# team_flag_jig.net
KiCad netlist of a schematic drawn in EAGLE
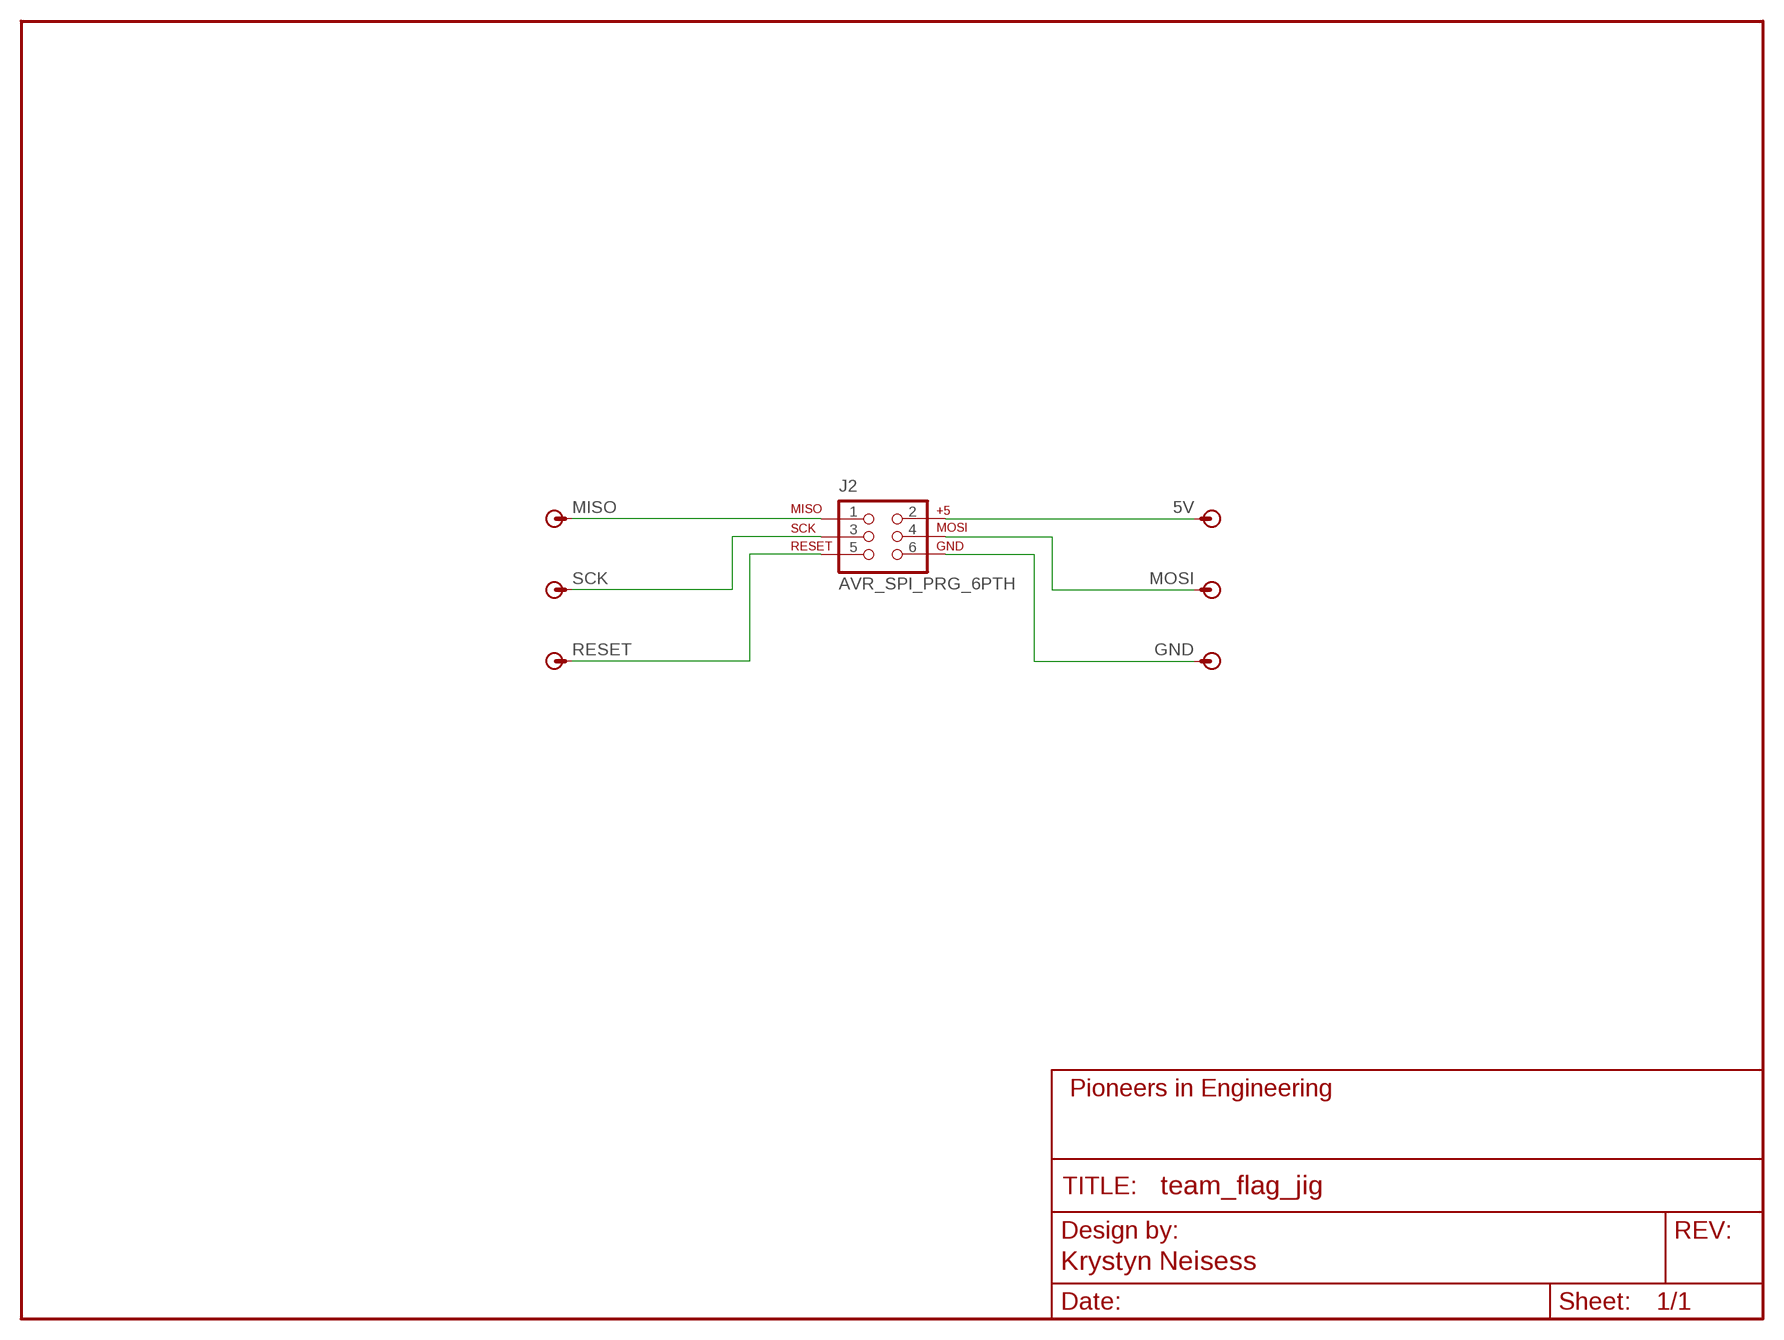
[diagram p0: schematic, sheet 1]

(export (version "E")
  (design (tool "Eeschema 10.0.6"))
  (components
    (comp (ref "5V")
      (value "POGO_PIN")
      (footprint "eagle-import:POGO_PIN_394")
      (libsource (lib "eagle-import") (part "POGO_PIN"))
    )
    (comp (ref "GND")
      (value "POGO_PIN")
      (footprint "eagle-import:POGO_PIN_394")
      (libsource (lib "eagle-import") (part "POGO_PIN"))
    )
    (comp (ref "J2")
      (value "AVR_SPI_PRG_6PTH")
      (footprint "eagle-import:2X3")
      (libsource (lib "eagle-import") (part "AVR_SPI_PRG_6PTH"))
    )
    (comp (ref "MISO")
      (value "POGO_PIN")
      (footprint "eagle-import:POGO_PIN_394")
      (libsource (lib "eagle-import") (part "POGO_PIN"))
    )
    (comp (ref "MOSI")
      (value "POGO_PIN")
      (footprint "eagle-import:POGO_PIN_394")
      (libsource (lib "eagle-import") (part "POGO_PIN"))
    )
    (comp (ref "RESET")
      (value "POGO_PIN")
      (footprint "eagle-import:POGO_PIN_394")
      (libsource (lib "eagle-import") (part "POGO_PIN"))
    )
    (comp (ref "SCK")
      (value "POGO_PIN")
      (footprint "eagle-import:POGO_PIN_394")
      (libsource (lib "eagle-import") (part "POGO_PIN"))
    )
  )
  (nets
    (net (code "1") (name "Net-(5V-P$1)") (class "Default")
      (node (ref "5V") (pin "POGO_PIN") (pinfunction "P$1_POGO_PIN") (pintype "bidirectional"))
      (node (ref "J2") (pin "2") (pinfunction "2_2") (pintype "passive"))
    )
    (net (code "2") (name "Net-(GND-P$1)") (class "Default")
      (node (ref "GND") (pin "POGO_PIN") (pinfunction "P$1_POGO_PIN") (pintype "bidirectional"))
      (node (ref "J2") (pin "6") (pinfunction "6_6") (pintype "passive"))
    )
    (net (code "3") (name "Net-(MISO-P$1)") (class "Default")
      (node (ref "J2") (pin "1") (pinfunction "1_1") (pintype "passive"))
      (node (ref "MISO") (pin "POGO_PIN") (pinfunction "P$1_POGO_PIN") (pintype "bidirectional"))
    )
    (net (code "4") (name "Net-(MOSI-P$1)") (class "Default")
      (node (ref "J2") (pin "4") (pinfunction "4_4") (pintype "passive"))
      (node (ref "MOSI") (pin "POGO_PIN") (pinfunction "P$1_POGO_PIN") (pintype "bidirectional"))
    )
    (net (code "5") (name "Net-(RESET-P$1)") (class "Default")
      (node (ref "J2") (pin "5") (pinfunction "5_5") (pintype "passive"))
      (node (ref "RESET") (pin "POGO_PIN") (pinfunction "P$1_POGO_PIN") (pintype "bidirectional"))
    )
    (net (code "6") (name "Net-(SCK-P$1)") (class "Default")
      (node (ref "J2") (pin "3") (pinfunction "3_3") (pintype "passive"))
      (node (ref "SCK") (pin "POGO_PIN") (pinfunction "P$1_POGO_PIN") (pintype "bidirectional"))
    )
  )
)
